# miditendo_rev1.net
KiCad netlist of a schematic drawn in EAGLE
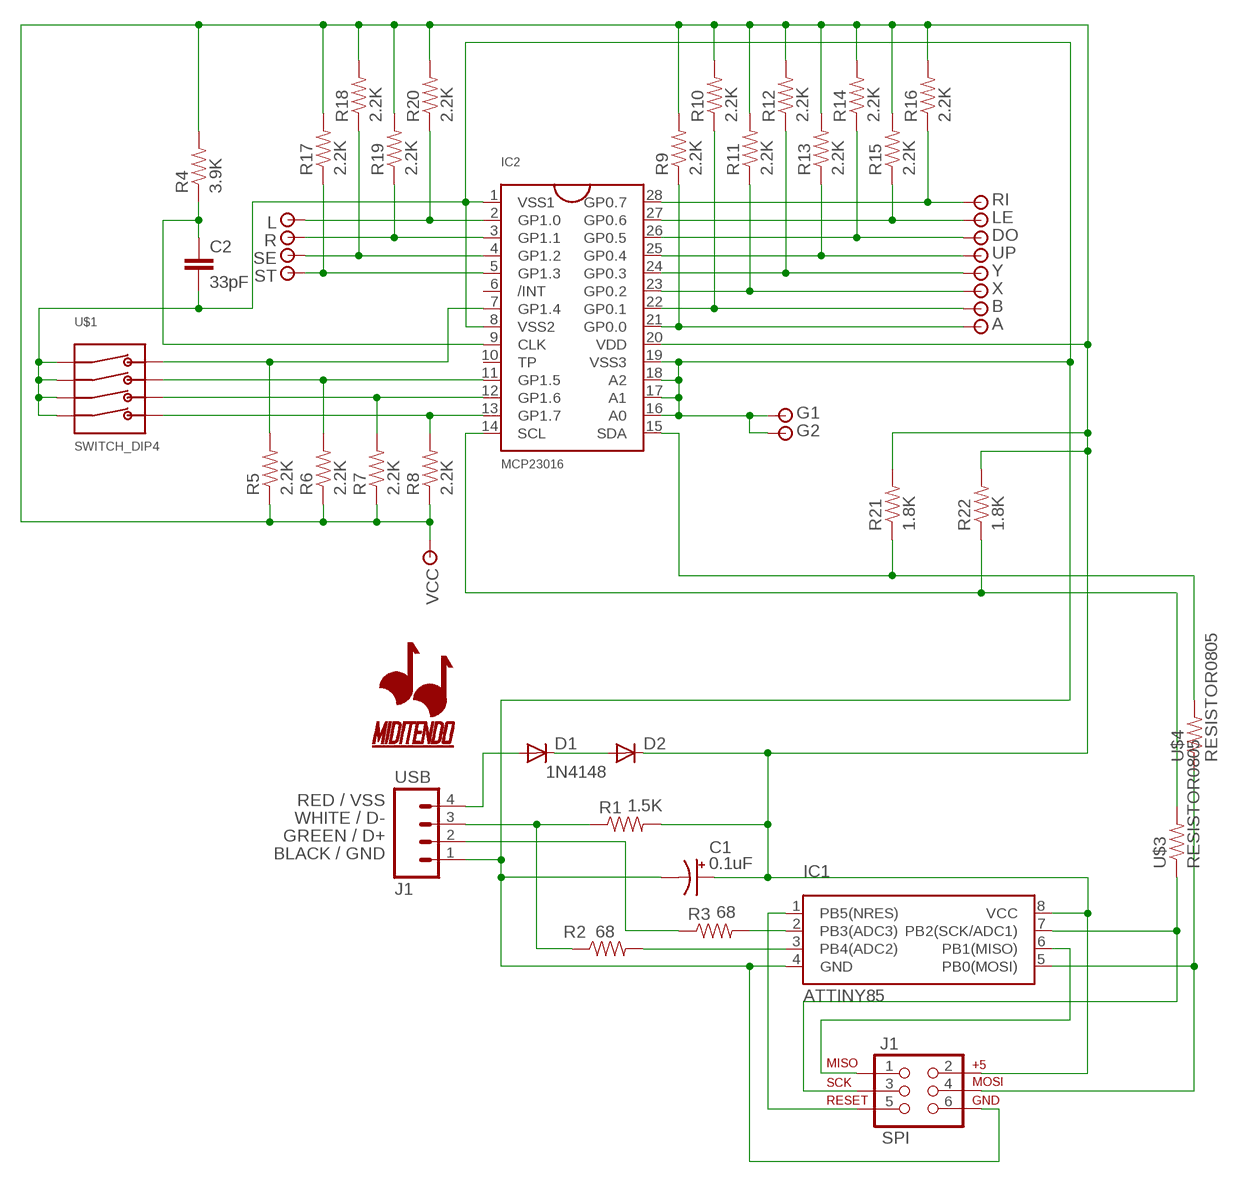
[diagram p0: schematic, sheet 1]

(export (version "E")
  (design (tool "Eeschema 10.0.6"))
  (components
    (comp (ref "A")
      (value "WIRE_JOINT")
      (footprint "eagle-import:THSOLDERPOINT")
      (libsource (lib "eagle-import") (part "WIRE_JOINT"))
    )
    (comp (ref "B")
      (value "WIRE_JOINT")
      (footprint "eagle-import:THSOLDERPOINT")
      (libsource (lib "eagle-import") (part "WIRE_JOINT"))
    )
    (comp (ref "C1")
      (value "0.1uF")
      (footprint "eagle-import:POLCAP_2.54")
      (libsource (lib "eagle-import") (part "POLARIZEDCAPACITORTH_2.54"))
    )
    (comp (ref "C2")
      (value "33pF")
      (footprint "eagle-import:0805")
      (libsource (lib "eagle-import") (part "CAPACITOR0805"))
    )
    (comp (ref "D1")
      (value "LL4148SOD-80C")
      (footprint "eagle-import:SOD-80C")
      (libsource (lib "eagle-import") (part "LL4148SOD-80C"))
    )
    (comp (ref "D2")
      (value "1N4148")
      (footprint "eagle-import:SOD-80C")
      (libsource (lib "eagle-import") (part "LL4148SOD-80C"))
    )
    (comp (ref "DO")
      (value "WIRE_JOINT")
      (footprint "eagle-import:THSOLDERPOINT")
      (libsource (lib "eagle-import") (part "WIRE_JOINT"))
    )
    (comp (ref "G1")
      (value "WIRE_JOINT")
      (footprint "eagle-import:THSOLDERPOINT")
      (libsource (lib "eagle-import") (part "WIRE_JOINT"))
    )
    (comp (ref "G2")
      (value "WIRE_JOINT")
      (footprint "eagle-import:THSOLDERPOINT")
      (libsource (lib "eagle-import") (part "WIRE_JOINT"))
    )
    (comp (ref "IC1")
      (value "ATTINY85")
      (footprint "eagle-import:SOIC8-EIAJ")
      (libsource (lib "eagle-import") (part "ATTINY85SOIC"))
    )
    (comp (ref "IC2")
      (value "MCP23016")
      (footprint "eagle-import:SOIC28")
      (libsource (lib "eagle-import") (part "MCP23016SOIC28"))
    )
    (comp (ref "J1")
      (value "SPI")
      (footprint "eagle-import:2X3-NS")
      (libsource (lib "eagle-import") (part "AVR_SPI_PRG_6NS"))
    )
    (comp (ref "L")
      (value "WIRE_JOINT")
      (footprint "eagle-import:THSOLDERPOINT")
      (libsource (lib "eagle-import") (part "WIRE_JOINT"))
    )
    (comp (ref "LE")
      (value "WIRE_JOINT")
      (footprint "eagle-import:THSOLDERPOINT")
      (libsource (lib "eagle-import") (part "WIRE_JOINT"))
    )
    (comp (ref "R")
      (value "WIRE_JOINT")
      (footprint "eagle-import:THSOLDERPOINT")
      (libsource (lib "eagle-import") (part "WIRE_JOINT"))
    )
    (comp (ref "R1")
      (value "1.5K")
      (footprint "eagle-import:0805")
      (libsource (lib "eagle-import") (part "RESISTOR0805"))
    )
    (comp (ref "R2")
      (value "68")
      (footprint "eagle-import:0805")
      (libsource (lib "eagle-import") (part "RESISTOR0805"))
    )
    (comp (ref "R3")
      (value "68")
      (footprint "eagle-import:0805")
      (libsource (lib "eagle-import") (part "RESISTOR0805"))
    )
    (comp (ref "R4")
      (value "3.9K")
      (footprint "eagle-import:0805")
      (libsource (lib "eagle-import") (part "RESISTOR0805"))
    )
    (comp (ref "R5")
      (value "2.2K")
      (footprint "eagle-import:0805")
      (libsource (lib "eagle-import") (part "RESISTOR0805"))
    )
    (comp (ref "R6")
      (value "2.2K")
      (footprint "eagle-import:0805")
      (libsource (lib "eagle-import") (part "RESISTOR0805"))
    )
    (comp (ref "R7")
      (value "2.2K")
      (footprint "eagle-import:0805")
      (libsource (lib "eagle-import") (part "RESISTOR0805"))
    )
    (comp (ref "R8")
      (value "2.2K")
      (footprint "eagle-import:0805")
      (libsource (lib "eagle-import") (part "RESISTOR0805"))
    )
    (comp (ref "R9")
      (value "2.2K")
      (footprint "eagle-import:0805")
      (libsource (lib "eagle-import") (part "RESISTOR0805"))
    )
    (comp (ref "R10")
      (value "2.2K")
      (footprint "eagle-import:0805")
      (libsource (lib "eagle-import") (part "RESISTOR0805"))
    )
    (comp (ref "R11")
      (value "2.2K")
      (footprint "eagle-import:0805")
      (libsource (lib "eagle-import") (part "RESISTOR0805"))
    )
    (comp (ref "R12")
      (value "2.2K")
      (footprint "eagle-import:0805")
      (libsource (lib "eagle-import") (part "RESISTOR0805"))
    )
    (comp (ref "R13")
      (value "2.2K")
      (footprint "eagle-import:0805")
      (libsource (lib "eagle-import") (part "RESISTOR0805"))
    )
    (comp (ref "R14")
      (value "2.2K")
      (footprint "eagle-import:0805")
      (libsource (lib "eagle-import") (part "RESISTOR0805"))
    )
    (comp (ref "R15")
      (value "2.2K")
      (footprint "eagle-import:0805")
      (libsource (lib "eagle-import") (part "RESISTOR0805"))
    )
    (comp (ref "R16")
      (value "2.2K")
      (footprint "eagle-import:0805")
      (libsource (lib "eagle-import") (part "RESISTOR0805"))
    )
    (comp (ref "R17")
      (value "2.2K")
      (footprint "eagle-import:0805")
      (libsource (lib "eagle-import") (part "RESISTOR0805"))
    )
    (comp (ref "R18")
      (value "2.2K")
      (footprint "eagle-import:0805")
      (libsource (lib "eagle-import") (part "RESISTOR0805"))
    )
    (comp (ref "R19")
      (value "2.2K")
      (footprint "eagle-import:0805")
      (libsource (lib "eagle-import") (part "RESISTOR0805"))
    )
    (comp (ref "R20")
      (value "2.2K")
      (footprint "eagle-import:0805")
      (libsource (lib "eagle-import") (part "RESISTOR0805"))
    )
    (comp (ref "R21")
      (value "1.8K")
      (footprint "eagle-import:0805")
      (libsource (lib "eagle-import") (part "RESISTOR0805"))
    )
    (comp (ref "R22")
      (value "1.8K")
      (footprint "eagle-import:0805")
      (libsource (lib "eagle-import") (part "RESISTOR0805"))
    )
    (comp (ref "RI")
      (value "WIRE_JOINT")
      (footprint "eagle-import:THSOLDERPOINT")
      (libsource (lib "eagle-import") (part "WIRE_JOINT"))
    )
    (comp (ref "SE")
      (value "WIRE_JOINT")
      (footprint "eagle-import:THSOLDERPOINT")
      (libsource (lib "eagle-import") (part "WIRE_JOINT"))
    )
    (comp (ref "ST")
      (value "WIRE_JOINT")
      (footprint "eagle-import:THSOLDERPOINT")
      (libsource (lib "eagle-import") (part "WIRE_JOINT"))
    )
    (comp (ref "U$1")
      (value "SWITCH_DIP4")
      (footprint "eagle-import:SWITCH_4DIP")
      (libsource (lib "eagle-import") (part "SWITCH_DIP4"))
    )
    (comp (ref "U$2")
      (value "MIDITENDO")
      (footprint "eagle-import:MIDITENDO")
      (libsource (lib "eagle-import") (part "MIDITENDO"))
    )
    (comp (ref "U$3")
      (value "RESISTOR0805")
      (footprint "eagle-import:0805")
      (libsource (lib "eagle-import") (part "RESISTOR0805"))
    )
    (comp (ref "U$4")
      (value "RESISTOR0805")
      (footprint "eagle-import:0805")
      (libsource (lib "eagle-import") (part "RESISTOR0805"))
    )
    (comp (ref "UP")
      (value "WIRE_JOINT")
      (footprint "eagle-import:THSOLDERPOINT")
      (libsource (lib "eagle-import") (part "WIRE_JOINT"))
    )
    (comp (ref "USB")
      (value "J1")
      (footprint "eagle-import:1X04_LONGPADS")
      (libsource (lib "eagle-import") (part "M04LONGPADS"))
    )
    (comp (ref "VCC")
      (value "WIRE_JOINT")
      (footprint "eagle-import:THSOLDERPOINT")
      (libsource (lib "eagle-import") (part "WIRE_JOINT"))
    )
    (comp (ref "X")
      (value "WIRE_JOINT")
      (footprint "eagle-import:THSOLDERPOINT")
      (libsource (lib "eagle-import") (part "WIRE_JOINT"))
    )
    (comp (ref "Y")
      (value "WIRE_JOINT")
      (footprint "eagle-import:THSOLDERPOINT")
      (libsource (lib "eagle-import") (part "WIRE_JOINT"))
    )
  )
  (nets
    (net (code "1") (name "Net-(C1-+)") (class "Default")
      (node (ref "C1") (pin "P") (pinfunction "+_P") (pintype "passive"))
      (node (ref "D2") (pin "PC") (pinfunction "C_PC") (pintype "passive"))
      (node (ref "IC1") (pin "8") (pinfunction "VCC_8") (pintype "bidirectional"))
      (node (ref "IC2") (pin "20") (pinfunction "VDD_20") (pintype "power_in"))
      (node (ref "J1") (pin "2") (pinfunction "2_2") (pintype "passive"))
      (node (ref "R1") (pin "2") (pinfunction "2_2") (pintype "passive"))
      (node (ref "R10") (pin "2") (pinfunction "2_2") (pintype "passive"))
      (node (ref "R11") (pin "2") (pinfunction "2_2") (pintype "passive"))
      (node (ref "R12") (pin "2") (pinfunction "2_2") (pintype "passive"))
      (node (ref "R13") (pin "2") (pinfunction "2_2") (pintype "passive"))
      (node (ref "R14") (pin "2") (pinfunction "2_2") (pintype "passive"))
      (node (ref "R15") (pin "2") (pinfunction "2_2") (pintype "passive"))
      (node (ref "R16") (pin "2") (pinfunction "2_2") (pintype "passive"))
      (node (ref "R17") (pin "2") (pinfunction "2_2") (pintype "passive"))
      (node (ref "R18") (pin "2") (pinfunction "2_2") (pintype "passive"))
      (node (ref "R19") (pin "2") (pinfunction "2_2") (pintype "passive"))
      (node (ref "R20") (pin "2") (pinfunction "2_2") (pintype "passive"))
      (node (ref "R21") (pin "2") (pinfunction "2_2") (pintype "passive"))
      (node (ref "R22") (pin "2") (pinfunction "2_2") (pintype "passive"))
      (node (ref "R4") (pin "2") (pinfunction "2_2") (pintype "passive"))
      (node (ref "R5") (pin "1") (pinfunction "1_1") (pintype "passive"))
      (node (ref "R6") (pin "1") (pinfunction "1_1") (pintype "passive"))
      (node (ref "R7") (pin "1") (pinfunction "1_1") (pintype "passive"))
      (node (ref "R8") (pin "1") (pinfunction "1_1") (pintype "passive"))
      (node (ref "R9") (pin "2") (pinfunction "2_2") (pintype "passive"))
      (node (ref "VCC") (pin "P$1") (pinfunction "P$1_P$1") (pintype "passive"))
    )
    (net (code "2") (name "Net-(C1--)") (class "Default")
      (node (ref "C1") (pin "N") (pinfunction "-_N") (pintype "passive"))
      (node (ref "C2") (pin "2") (pinfunction "2_2") (pintype "passive"))
      (node (ref "G1") (pin "P$1") (pinfunction "P$1_P$1") (pintype "passive"))
      (node (ref "G2") (pin "P$1") (pinfunction "P$1_P$1") (pintype "passive"))
      (node (ref "IC1") (pin "4") (pinfunction "GND_4") (pintype "bidirectional"))
      (node (ref "IC2") (pin "1") (pinfunction "VSS1_1") (pintype "power_in"))
      (node (ref "IC2") (pin "16") (pinfunction "A0_16") (pintype "input"))
      (node (ref "IC2") (pin "17") (pinfunction "A1_17") (pintype "input"))
      (node (ref "IC2") (pin "18") (pinfunction "A2_18") (pintype "input"))
      (node (ref "IC2") (pin "19") (pinfunction "VSS3_19") (pintype "power_in"))
      (node (ref "IC2") (pin "8") (pinfunction "VSS2_8") (pintype "power_in"))
      (node (ref "J1") (pin "6") (pinfunction "6_6") (pintype "passive"))
      (node (ref "U$1") (pin "P$1") (pinfunction "P$1_P$1") (pintype "passive"))
      (node (ref "U$1") (pin "P$2") (pinfunction "P$2_P$2") (pintype "passive"))
      (node (ref "U$1") (pin "P$3") (pinfunction "P$3_P$3") (pintype "passive"))
      (node (ref "U$1") (pin "P$4") (pinfunction "P$4_P$4") (pintype "passive"))
      (node (ref "USB") (pin "1") (pinfunction "1_1") (pintype "passive"))
    )
    (net (code "3") (name "Net-(D1-A)") (class "Default")
      (node (ref "D1") (pin "PA") (pinfunction "A_PA") (pintype "passive"))
      (node (ref "USB") (pin "4") (pinfunction "4_4") (pintype "passive"))
    )
    (net (code "4") (name "Net-(D1-C)") (class "Default")
      (node (ref "D1") (pin "PC") (pinfunction "C_PC") (pintype "passive"))
      (node (ref "D2") (pin "PA") (pinfunction "A_PA") (pintype "passive"))
    )
    (net (code "5") (name "Net-(IC1-PB0(MOSI))") (class "Default")
      (node (ref "IC1") (pin "5") (pinfunction "PB0(MOSI)_5") (pintype "bidirectional"))
      (node (ref "J1") (pin "4") (pinfunction "4_4") (pintype "passive"))
      (node (ref "U$4") (pin "1") (pinfunction "1_1") (pintype "passive"))
    )
    (net (code "6") (name "Net-(IC1-PB1(MISO))") (class "Default")
      (node (ref "IC1") (pin "6") (pinfunction "PB1(MISO)_6") (pintype "bidirectional"))
      (node (ref "J1") (pin "1") (pinfunction "1_1") (pintype "passive"))
    )
    (net (code "7") (name "Net-(IC1-PB2(SCK{slash}ADC1))") (class "Default")
      (node (ref "IC1") (pin "7") (pinfunction "PB2(SCK/ADC1)_7") (pintype "bidirectional"))
      (node (ref "J1") (pin "3") (pinfunction "3_3") (pintype "passive"))
      (node (ref "U$3") (pin "1") (pinfunction "1_1") (pintype "passive"))
    )
    (net (code "8") (name "Net-(IC1-PB3(ADC3))") (class "Default")
      (node (ref "IC1") (pin "2") (pinfunction "PB3(ADC3)_2") (pintype "bidirectional"))
      (node (ref "R3") (pin "2") (pinfunction "2_2") (pintype "passive"))
    )
    (net (code "9") (name "Net-(IC1-PB4(ADC2))") (class "Default")
      (node (ref "IC1") (pin "3") (pinfunction "PB4(ADC2)_3") (pintype "bidirectional"))
      (node (ref "R2") (pin "2") (pinfunction "2_2") (pintype "passive"))
    )
    (net (code "10") (name "Net-(IC1-PB5(NRES))") (class "Default")
      (node (ref "IC1") (pin "1") (pinfunction "PB5(NRES)_1") (pintype "bidirectional"))
      (node (ref "J1") (pin "5") (pinfunction "5_5") (pintype "passive"))
    )
    (net (code "11") (name "Net-(IC2-CLK)") (class "Default")
      (node (ref "C2") (pin "1") (pinfunction "1_1") (pintype "passive"))
      (node (ref "IC2") (pin "9") (pinfunction "CLK_9") (pintype "input"))
      (node (ref "R4") (pin "1") (pinfunction "1_1") (pintype "passive"))
    )
    (net (code "12") (name "Net-(IC2-GP0.0)") (class "Default")
      (node (ref "A") (pin "P$1") (pinfunction "P$1_P$1") (pintype "passive"))
      (node (ref "IC2") (pin "21") (pinfunction "GP0.0_21") (pintype "bidirectional"))
      (node (ref "R9") (pin "1") (pinfunction "1_1") (pintype "passive"))
    )
    (net (code "13") (name "Net-(IC2-GP0.1)") (class "Default")
      (node (ref "B") (pin "P$1") (pinfunction "P$1_P$1") (pintype "passive"))
      (node (ref "IC2") (pin "22") (pinfunction "GP0.1_22") (pintype "bidirectional"))
      (node (ref "R10") (pin "1") (pinfunction "1_1") (pintype "passive"))
    )
    (net (code "14") (name "Net-(IC2-GP0.2)") (class "Default")
      (node (ref "IC2") (pin "23") (pinfunction "GP0.2_23") (pintype "bidirectional"))
      (node (ref "R11") (pin "1") (pinfunction "1_1") (pintype "passive"))
      (node (ref "X") (pin "P$1") (pinfunction "P$1_P$1") (pintype "passive"))
    )
    (net (code "15") (name "Net-(IC2-GP0.3)") (class "Default")
      (node (ref "IC2") (pin "24") (pinfunction "GP0.3_24") (pintype "bidirectional"))
      (node (ref "R12") (pin "1") (pinfunction "1_1") (pintype "passive"))
      (node (ref "Y") (pin "P$1") (pinfunction "P$1_P$1") (pintype "passive"))
    )
    (net (code "16") (name "Net-(IC2-GP0.4)") (class "Default")
      (node (ref "IC2") (pin "25") (pinfunction "GP0.4_25") (pintype "bidirectional"))
      (node (ref "R13") (pin "1") (pinfunction "1_1") (pintype "passive"))
      (node (ref "UP") (pin "P$1") (pinfunction "P$1_P$1") (pintype "passive"))
    )
    (net (code "17") (name "Net-(IC2-GP0.5)") (class "Default")
      (node (ref "DO") (pin "P$1") (pinfunction "P$1_P$1") (pintype "passive"))
      (node (ref "IC2") (pin "26") (pinfunction "GP0.5_26") (pintype "bidirectional"))
      (node (ref "R14") (pin "1") (pinfunction "1_1") (pintype "passive"))
    )
    (net (code "18") (name "Net-(IC2-GP0.6)") (class "Default")
      (node (ref "IC2") (pin "27") (pinfunction "GP0.6_27") (pintype "bidirectional"))
      (node (ref "LE") (pin "P$1") (pinfunction "P$1_P$1") (pintype "passive"))
      (node (ref "R15") (pin "1") (pinfunction "1_1") (pintype "passive"))
    )
    (net (code "19") (name "Net-(IC2-GP0.7)") (class "Default")
      (node (ref "IC2") (pin "28") (pinfunction "GP0.7_28") (pintype "bidirectional"))
      (node (ref "R16") (pin "1") (pinfunction "1_1") (pintype "passive"))
      (node (ref "RI") (pin "P$1") (pinfunction "P$1_P$1") (pintype "passive"))
    )
    (net (code "20") (name "Net-(IC2-GP1.0)") (class "Default")
      (node (ref "IC2") (pin "2") (pinfunction "GP1.0_2") (pintype "bidirectional"))
      (node (ref "L") (pin "P$1") (pinfunction "P$1_P$1") (pintype "passive"))
      (node (ref "R20") (pin "1") (pinfunction "1_1") (pintype "passive"))
    )
    (net (code "21") (name "Net-(IC2-GP1.1)") (class "Default")
      (node (ref "IC2") (pin "3") (pinfunction "GP1.1_3") (pintype "bidirectional"))
      (node (ref "R") (pin "P$1") (pinfunction "P$1_P$1") (pintype "passive"))
      (node (ref "R19") (pin "1") (pinfunction "1_1") (pintype "passive"))
    )
    (net (code "22") (name "Net-(IC2-GP1.2)") (class "Default")
      (node (ref "IC2") (pin "4") (pinfunction "GP1.2_4") (pintype "bidirectional"))
      (node (ref "R18") (pin "1") (pinfunction "1_1") (pintype "passive"))
      (node (ref "SE") (pin "P$1") (pinfunction "P$1_P$1") (pintype "passive"))
    )
    (net (code "23") (name "Net-(IC2-GP1.3)") (class "Default")
      (node (ref "IC2") (pin "5") (pinfunction "GP1.3_5") (pintype "bidirectional"))
      (node (ref "R17") (pin "1") (pinfunction "1_1") (pintype "passive"))
      (node (ref "ST") (pin "P$1") (pinfunction "P$1_P$1") (pintype "passive"))
    )
    (net (code "24") (name "Net-(IC2-GP1.4)") (class "Default")
      (node (ref "IC2") (pin "7") (pinfunction "GP1.4_7") (pintype "bidirectional"))
      (node (ref "R5") (pin "2") (pinfunction "2_2") (pintype "passive"))
      (node (ref "U$1") (pin "P$8") (pinfunction "P$8_P$8") (pintype "passive"))
    )
    (net (code "25") (name "Net-(IC2-GP1.5)") (class "Default")
      (node (ref "IC2") (pin "11") (pinfunction "GP1.5_11") (pintype "bidirectional"))
      (node (ref "R6") (pin "2") (pinfunction "2_2") (pintype "passive"))
      (node (ref "U$1") (pin "P$7") (pinfunction "P$7_P$7") (pintype "passive"))
    )
    (net (code "26") (name "Net-(IC2-GP1.6)") (class "Default")
      (node (ref "IC2") (pin "12") (pinfunction "GP1.6_12") (pintype "bidirectional"))
      (node (ref "R7") (pin "2") (pinfunction "2_2") (pintype "passive"))
      (node (ref "U$1") (pin "P$6") (pinfunction "P$6_P$6") (pintype "passive"))
    )
    (net (code "27") (name "Net-(IC2-GP1.7)") (class "Default")
      (node (ref "IC2") (pin "13") (pinfunction "GP1.7_13") (pintype "bidirectional"))
      (node (ref "R8") (pin "2") (pinfunction "2_2") (pintype "passive"))
      (node (ref "U$1") (pin "P$5") (pinfunction "P$5_P$5") (pintype "passive"))
    )
    (net (code "28") (name "Net-(IC2-SCL)") (class "Default")
      (node (ref "IC2") (pin "14") (pinfunction "SCL_14") (pintype "input"))
      (node (ref "R22") (pin "1") (pinfunction "1_1") (pintype "passive"))
      (node (ref "U$3") (pin "2") (pinfunction "2_2") (pintype "passive"))
    )
    (net (code "29") (name "Net-(IC2-SDA)") (class "Default")
      (node (ref "IC2") (pin "15") (pinfunction "SDA_15") (pintype "bidirectional"))
      (node (ref "R21") (pin "1") (pinfunction "1_1") (pintype "passive"))
      (node (ref "U$4") (pin "2") (pinfunction "2_2") (pintype "passive"))
    )
    (net (code "30") (name "Net-(R1-Pad1)") (class "Default")
      (node (ref "R1") (pin "1") (pinfunction "1_1") (pintype "passive"))
      (node (ref "R2") (pin "1") (pinfunction "1_1") (pintype "passive"))
      (node (ref "USB") (pin "3") (pinfunction "3_3") (pintype "passive"))
    )
    (net (code "31") (name "Net-(R3-Pad1)") (class "Default")
      (node (ref "R3") (pin "1") (pinfunction "1_1") (pintype "passive"))
      (node (ref "USB") (pin "2") (pinfunction "2_2") (pintype "passive"))
    )
    (net (code "32") (name "unconnected-(IC2-TP-Pad10)") (class "Default")
      (node (ref "IC2") (pin "10") (pinfunction "TP_10") (pintype "bidirectional"))
    )
    (net (code "33") (name "unconnected-(IC2-{slash}INT-Pad6)") (class "Default")
      (node (ref "IC2") (pin "6") (pinfunction "/INT_6") (pintype "output"))
    )
  )
)
